# PowerDevices.net
KiCad netlist of a schematic drawn in Altium Designer
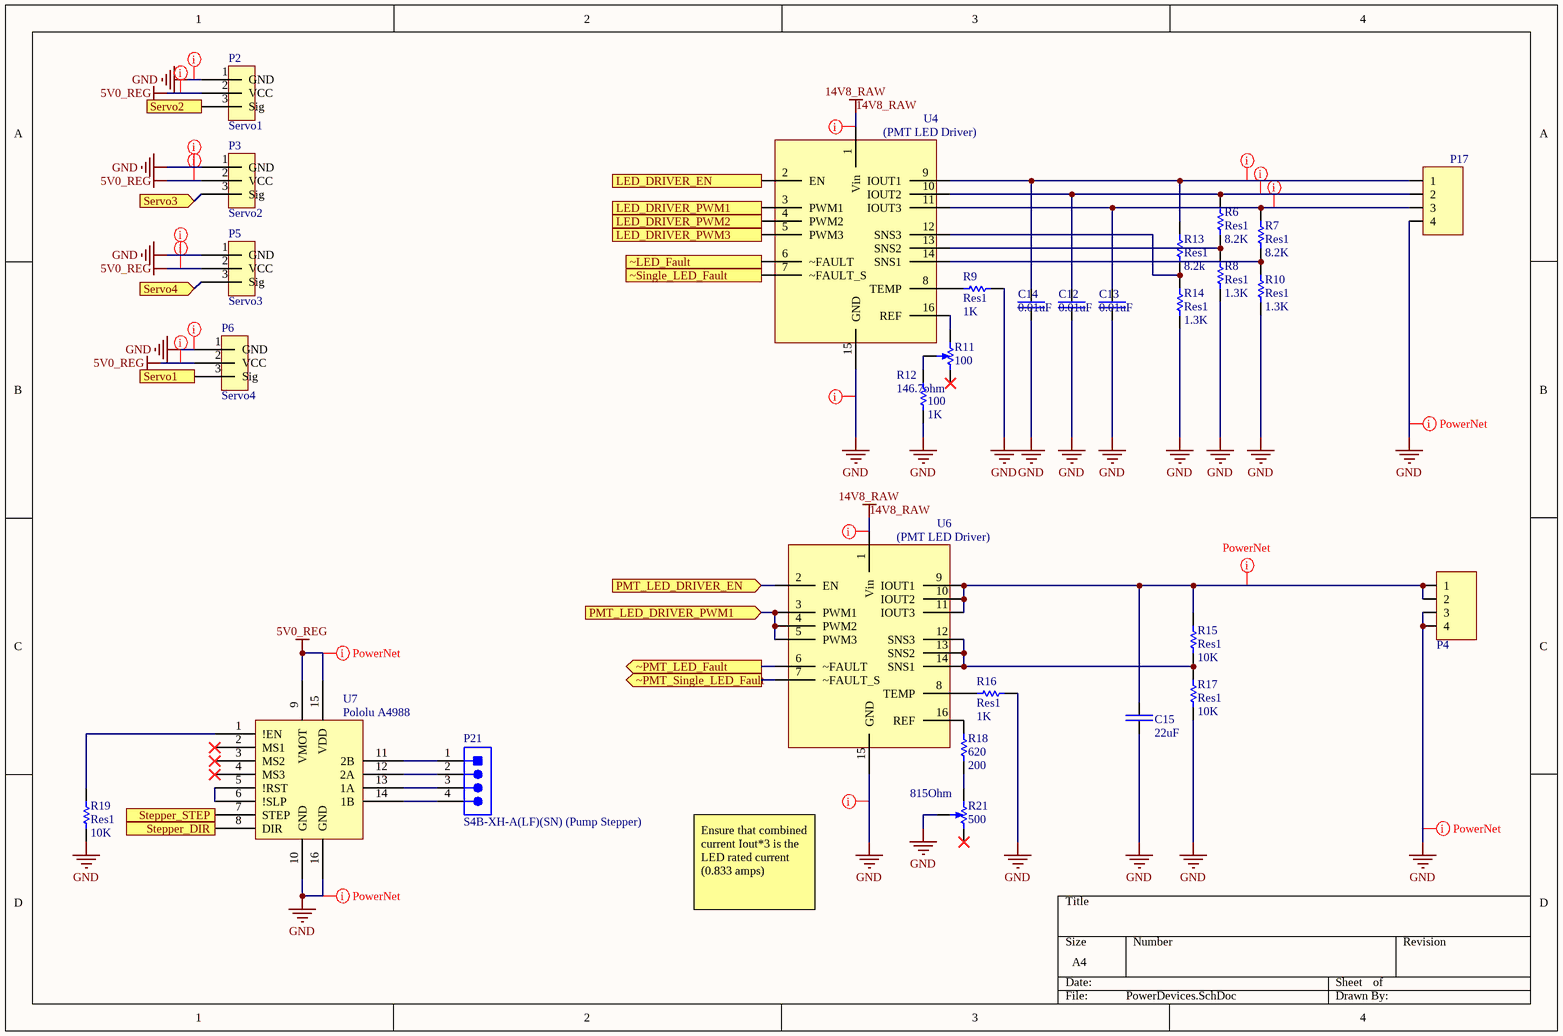
[diagram p0: PowerDevices.SchDoc]

(export (version "E")
  (design (tool "Eeschema 10.0.6"))
  (components
    (comp (ref "C12")
      (value "0.01uF")
      (footprint "0.01uF capacitor")
      (description "Cap Ceramic 0.01uF 250V X7R 10% Pad SMD 0603 125C Automotive T/R")
      (fields (field (name "TOLERANCE") "10%"))
      (libsource (lib "RSX_Capacitors") (part "C0603C103KARACAUTO"))
    )
    (comp (ref "C13")
      (value "0.01uF")
      (footprint "0.01uF capacitor")
      (description "Cap Ceramic 0.01uF 250V X7R 10% Pad SMD 0603 125C Automotive T/R")
      (fields (field (name "TOLERANCE") "10%"))
      (libsource (lib "RSX_Capacitors") (part "C0603C103KARACAUTO"))
    )
    (comp (ref "C14")
      (value "0.01uF")
      (footprint "0.01uF capacitor")
      (description "Cap Ceramic 0.01uF 250V X7R 10% Pad SMD 0603 125C Automotive T/R")
      (fields (field (name "TOLERANCE") "10%"))
      (libsource (lib "RSX_Capacitors") (part "C0603C103KARACAUTO"))
    )
    (comp (ref "C15")
      (value "22uF")
      (footprint "22uF Capacitor")
      (description "Cap Ceramic 22uF 25V X7R 10% SMD 1210 125C Embossed T/R")
      (fields (field (name "TOLERANCE") "10%") (field (name "VOLTAGE") "25V"))
      (libsource (lib "RSX_Capacitors") (part "GRM32ER71E226KE15L"))
    )
    (comp (ref "P2") (value "Servo1") (footprint "Header3") (libsource (lib "DUE") (part "Header3")))
    (comp (ref "P3") (value "Servo2") (footprint "Header3") (libsource (lib "DUE") (part "Header3")))
    (comp (ref "P4")
      (value "Mini-Fit Jr 4 Pos")
      (footprint "MOLEX 0039281043")
      (libsource (lib "RSX_Connectors") (part "Molex 0039281043"))
    )
    (comp (ref "P5") (value "Servo3") (footprint "Header3") (libsource (lib "DUE") (part "Header3")))
    (comp (ref "P6") (value "Servo4") (footprint "Header3") (libsource (lib "DUE") (part "Header3")))
    (comp (ref "P17")
      (value "Mini-Fit Jr 4 Pos")
      (footprint "MOLEX 0039281043")
      (libsource (lib "RSX_Connectors") (part "Molex 0039281043"))
    )
    (comp (ref "P21")
      (value "S4B-XH-A(LF)(SN) (Pump Stepper)")
      (footprint "JST-S4B-XH-A(LF)(SN)_V")
      (libsource (lib "Altium Content Vault") (part "CN-1P-M-R4"))
    )
    (comp (ref "R6")
      (value "Res1")
      (footprint "RESC1608X06N_0603")
      (description "Resistor")
      (fields (field (name "ALTIUM_VALUE") "8.2K") (field (name "PUBLISHER") "Altium Limited"))
      (libsource (lib "RSX_Resistors") (part "Res1"))
    )
    (comp (ref "R7")
      (value "Res1")
      (footprint "RESC1608X06N_0603")
      (description "Resistor")
      (fields (field (name "ALTIUM_VALUE") "8.2K") (field (name "PUBLISHER") "Altium Limited"))
      (libsource (lib "RSX_Resistors") (part "Res1"))
    )
    (comp (ref "R8")
      (value "Res1")
      (footprint "RESC1608X06N_0603")
      (description "Resistor")
      (fields (field (name "ALTIUM_VALUE") "1.3K") (field (name "PUBLISHER") "Altium Limited"))
      (libsource (lib "RSX_Resistors") (part "Res1"))
    )
    (comp (ref "R9")
      (value "Res1")
      (footprint "RESC1608X06N_0603")
      (description "Resistor")
      (fields (field (name "ALTIUM_VALUE") "1K") (field (name "PUBLISHER") "Altium Limited"))
      (libsource (lib "RSX_Resistors") (part "Res1"))
    )
    (comp (ref "R10")
      (value "Res1")
      (footprint "RESC1608X06N_0603")
      (description "Resistor")
      (fields (field (name "ALTIUM_VALUE") "1.3K") (field (name "PUBLISHER") "Altium Limited"))
      (libsource (lib "RSX_Resistors") (part "Res1"))
    )
    (comp (ref "R11")
      (value "100")
      (footprint "POT-LV10")
      (description "Square Trimming Potentiometer (100 ohm)")
      (fields (field (name "PUBLISHER") "Altium Limited"))
      (libsource (lib "Miscellaneous Devices") (part "RPot SM"))
    )
    (comp (ref "R12")
      (value "100")
      (footprint "RESC1608X06N_0603")
      (description "Resistor")
      (fields (field (name "ALTIUM_VALUE") "1K") (field (name "PUBLISHER") "Altium Limited"))
      (libsource (lib "RSX_Resistors") (part "Res1"))
    )
    (comp (ref "R13")
      (value "Res1")
      (footprint "RESC1608X06N_0603")
      (description "Resistor")
      (fields (field (name "ALTIUM_VALUE") "8.2k") (field (name "PUBLISHER") "Altium Limited"))
      (libsource (lib "RSX_Resistors") (part "Res1"))
    )
    (comp (ref "R14")
      (value "Res1")
      (footprint "RESC1608X06N_0603")
      (description "Resistor")
      (fields (field (name "ALTIUM_VALUE") "1.3K") (field (name "PUBLISHER") "Altium Limited"))
      (libsource (lib "RSX_Resistors") (part "Res1"))
    )
    (comp (ref "R15")
      (value "Res1")
      (footprint "RESC1608X06N_0603")
      (description "Resistor")
      (fields (field (name "ALTIUM_VALUE") "10K") (field (name "PUBLISHER") "Altium Limited"))
      (libsource (lib "RSX_Resistors") (part "Res1"))
    )
    (comp (ref "R16")
      (value "Res1")
      (footprint "RESC1608X06N_0603")
      (description "Resistor")
      (fields (field (name "ALTIUM_VALUE") "1K") (field (name "PUBLISHER") "Altium Limited"))
      (libsource (lib "RSX_Resistors") (part "Res1"))
    )
    (comp (ref "R17")
      (value "Res1")
      (footprint "RESC1608X06N_0603")
      (description "Resistor")
      (fields (field (name "ALTIUM_VALUE") "10K") (field (name "PUBLISHER") "Altium Limited"))
      (libsource (lib "RSX_Resistors") (part "Res1"))
    )
    (comp (ref "R18")
      (value "620")
      (footprint "RESC1608X06N_0603")
      (description "Resistor")
      (fields (field (name "ALTIUM_VALUE") "200") (field (name "PUBLISHER") "Altium Limited"))
      (libsource (lib "RSX_Resistors") (part "Res1"))
    )
    (comp (ref "R19")
      (value "Res1")
      (footprint "RESC1608X06N_0603")
      (description "Resistor")
      (fields (field (name "ALTIUM_VALUE") "10K") (field (name "PUBLISHER") "Altium Limited"))
      (libsource (lib "RSX_Resistors") (part "Res1"))
    )
    (comp (ref "R21")
      (value "500")
      (footprint "POT-LV10")
      (description "Square Trimming Potentiometer (100 ohm)")
      (fields (field (name "PUBLISHER") "Altium Limited"))
      (libsource (lib "Miscellaneous Devices") (part "RPot SM"))
    )
    (comp (ref "U4")
      (value "(PMT LED Driver)")
      (footprint "HTSSOP16")
      (libsource (lib "ScienceComponents") (part "TPS92630QPWPRQ1"))
    )
    (comp (ref "U6")
      (value "(PMT LED Driver)")
      (footprint "HTSSOP16")
      (libsource (lib "ScienceComponents") (part "TPS92630QPWPRQ1"))
    )
    (comp (ref "U7")
      (value "Pololu A4988")
      (footprint "Stepper Driver Pololu A4988")
      (libsource (lib "ScienceComponents") (part "stepper driver Pololu a4988"))
    )
  )
  (nets
    (net (code "1") (name "/LED_DRIVER_EN") (class "Default")
      (node (ref "U4") (pin "2") (pinfunction "EN_2") (pintype "passive"))
    )
    (net (code "2") (name "/LED_DRIVER_PWM1") (class "Default")
      (node (ref "U4") (pin "3") (pinfunction "PWM1_3") (pintype "passive"))
    )
    (net (code "3") (name "/LED_DRIVER_PWM2") (class "Default")
      (node (ref "U4") (pin "4") (pinfunction "PWM2_4") (pintype "passive"))
    )
    (net (code "4") (name "/LED_DRIVER_PWM3") (class "Default")
      (node (ref "U4") (pin "5") (pinfunction "PWM3_5") (pintype "passive"))
    )
    (net (code "5") (name "/PMT_LED_DRIVER_EN") (class "Default")
      (node (ref "U6") (pin "2") (pinfunction "EN_2") (pintype "passive"))
    )
    (net (code "6") (name "/PMT_LED_DRIVER_PWM1") (class "Default")
      (node (ref "U6") (pin "3") (pinfunction "PWM1_3") (pintype "passive"))
      (node (ref "U6") (pin "4") (pinfunction "PWM2_4") (pintype "passive"))
      (node (ref "U6") (pin "5") (pinfunction "PWM3_5") (pintype "passive"))
    )
    (net (code "7") (name "/Servo1") (class "Default")
      (node (ref "P6") (pin "3") (pinfunction "Sig_3") (pintype "passive"))
    )
    (net (code "8") (name "/Servo2") (class "Default")
      (node (ref "P2") (pin "3") (pinfunction "Sig_3") (pintype "passive"))
    )
    (net (code "9") (name "/Servo3") (class "Default")
      (node (ref "P3") (pin "3") (pinfunction "Sig_3") (pintype "passive"))
    )
    (net (code "10") (name "/Servo4") (class "Default")
      (node (ref "P5") (pin "3") (pinfunction "Sig_3") (pintype "passive"))
    )
    (net (code "11") (name "/Stepper_DIR") (class "Default")
      (node (ref "U7") (pin "8") (pinfunction "DIR_8") (pintype "passive"))
    )
    (net (code "12") (name "/Stepper_STEP") (class "Default")
      (node (ref "U7") (pin "7") (pinfunction "STEP_7") (pintype "passive"))
    )
    (net (code "13") (name "/~LED_Fault") (class "Default")
      (node (ref "U4") (pin "6") (pinfunction "~FAULT_6") (pintype "passive"))
    )
    (net (code "14") (name "/~PMT_LED_Fault") (class "Default")
      (node (ref "U6") (pin "6") (pinfunction "~FAULT_6") (pintype "passive"))
    )
    (net (code "15") (name "/~PMT_Single_LED_Fault") (class "Default")
      (node (ref "U6") (pin "7") (pinfunction "~FAULT_S_7") (pintype "passive"))
    )
    (net (code "16") (name "/~Single_LED_Fault") (class "Default")
      (node (ref "U4") (pin "7") (pinfunction "~FAULT_S_7") (pintype "passive"))
    )
    (net (code "17") (name "5V0_REG") (class "Default")
      (node (ref "P2") (pin "2") (pinfunction "VCC_2") (pintype "passive"))
      (node (ref "P3") (pin "2") (pinfunction "VCC_2") (pintype "passive"))
      (node (ref "P5") (pin "2") (pinfunction "VCC_2") (pintype "passive"))
      (node (ref "P6") (pin "2") (pinfunction "VCC_2") (pintype "passive"))
      (node (ref "U7") (pin "15") (pinfunction "VDD_15") (pintype "passive"))
      (node (ref "U7") (pin "9") (pinfunction "VMOT_9") (pintype "passive"))
    )
    (net (code "18") (name "14V8_RAW") (class "Default")
      (node (ref "U4") (pin "1") (pinfunction "Vin_1") (pintype "passive"))
      (node (ref "U6") (pin "1") (pinfunction "Vin_1") (pintype "passive"))
    )
    (net (code "19") (name "GND") (class "Default")
      (node (ref "C12") (pin "1") (pinfunction "15_1") (pintype "passive"))
      (node (ref "C13") (pin "1") (pinfunction "15_1") (pintype "passive"))
      (node (ref "C14") (pin "1") (pinfunction "15_1") (pintype "passive"))
      (node (ref "C15") (pin "1") (pinfunction "15_1") (pintype "passive"))
      (node (ref "P17") (pin "4") (pinfunction "4_4") (pintype "passive"))
      (node (ref "P2") (pin "1") (pinfunction "GND_1") (pintype "passive"))
      (node (ref "P3") (pin "1") (pinfunction "GND_1") (pintype "passive"))
      (node (ref "P4") (pin "3") (pinfunction "3_3") (pintype "passive"))
      (node (ref "P4") (pin "4") (pinfunction "4_4") (pintype "passive"))
      (node (ref "P5") (pin "1") (pinfunction "GND_1") (pintype "passive"))
      (node (ref "P6") (pin "1") (pinfunction "GND_1") (pintype "passive"))
      (node (ref "R10") (pin "1") (pinfunction "1_1") (pintype "passive"))
      (node (ref "R12") (pin "2") (pinfunction "2_2") (pintype "passive"))
      (node (ref "R14") (pin "1") (pinfunction "1_1") (pintype "passive"))
      (node (ref "R16") (pin "2") (pinfunction "2_2") (pintype "passive"))
      (node (ref "R17") (pin "1") (pinfunction "1_1") (pintype "passive"))
      (node (ref "R19") (pin "1") (pinfunction "1_1") (pintype "passive"))
      (node (ref "R21") (pin "W") (pinfunction "W_W") (pintype "passive"))
      (node (ref "R8") (pin "1") (pinfunction "1_1") (pintype "passive"))
      (node (ref "R9") (pin "2") (pinfunction "2_2") (pintype "passive"))
      (node (ref "U4") (pin "15") (pinfunction "GND_15") (pintype "passive"))
      (node (ref "U6") (pin "15") (pinfunction "GND_15") (pintype "passive"))
      (node (ref "U7") (pin "10") (pinfunction "GND_10") (pintype "passive"))
      (node (ref "U7") (pin "16") (pinfunction "GND_16") (pintype "passive"))
    )
    (net (code "20") (name "Net-(C12-16)") (class "Default")
      (node (ref "C12") (pin "2") (pinfunction "16_2") (pintype "passive"))
      (node (ref "P17") (pin "2") (pinfunction "2_2") (pintype "passive"))
      (node (ref "R6") (pin "2") (pinfunction "2_2") (pintype "passive"))
      (node (ref "U4") (pin "10") (pinfunction "IOUT2_10") (pintype "passive"))
    )
    (net (code "21") (name "Net-(C13-16)") (class "Default")
      (node (ref "C13") (pin "2") (pinfunction "16_2") (pintype "passive"))
      (node (ref "P17") (pin "3") (pinfunction "3_3") (pintype "passive"))
      (node (ref "R7") (pin "2") (pinfunction "2_2") (pintype "passive"))
      (node (ref "U4") (pin "11") (pinfunction "IOUT3_11") (pintype "passive"))
    )
    (net (code "22") (name "Net-(C14-16)") (class "Default")
      (node (ref "C14") (pin "2") (pinfunction "16_2") (pintype "passive"))
      (node (ref "P17") (pin "1") (pinfunction "1_1") (pintype "passive"))
      (node (ref "R13") (pin "1") (pinfunction "1_1") (pintype "passive"))
      (node (ref "U4") (pin "9") (pinfunction "IOUT1_9") (pintype "passive"))
    )
    (net (code "23") (name "Net-(C15-16)") (class "Default")
      (node (ref "C15") (pin "2") (pinfunction "16_2") (pintype "passive"))
      (node (ref "P4") (pin "1") (pinfunction "1_1") (pintype "passive"))
      (node (ref "P4") (pin "2") (pinfunction "2_2") (pintype "passive"))
      (node (ref "R15") (pin "1") (pinfunction "1_1") (pintype "passive"))
      (node (ref "U6") (pin "10") (pinfunction "IOUT2_10") (pintype "passive"))
      (node (ref "U6") (pin "11") (pinfunction "IOUT3_11") (pintype "passive"))
      (node (ref "U6") (pin "9") (pinfunction "IOUT1_9") (pintype "passive"))
    )
    (net (code "24") (name "Net-(R11--)") (class "Default")
      (node (ref "R11") (pin "CCW") (pinfunction "-_CCW") (pintype "passive"))
      (node (ref "U4") (pin "16") (pinfunction "REF_16") (pintype "passive"))
    )
    (net (code "25") (name "Net-(R11-PadW)") (class "Default")
      (node (ref "R11") (pin "W") (pinfunction "W_W") (pintype "passive"))
      (node (ref "R12") (pin "1") (pinfunction "1_1") (pintype "passive"))
    )
    (net (code "26") (name "Net-(R21--)") (class "Default")
      (node (ref "R18") (pin "1") (pinfunction "1_1") (pintype "passive"))
      (node (ref "R21") (pin "CCW") (pinfunction "-_CCW") (pintype "passive"))
    )
    (net (code "27") (name "Net-(U4-SNS1)") (class "Default")
      (node (ref "R10") (pin "2") (pinfunction "2_2") (pintype "passive"))
      (node (ref "R7") (pin "1") (pinfunction "1_1") (pintype "passive"))
      (node (ref "U4") (pin "14") (pinfunction "SNS1_14") (pintype "passive"))
    )
    (net (code "28") (name "Net-(U4-SNS2)") (class "Default")
      (node (ref "R6") (pin "1") (pinfunction "1_1") (pintype "passive"))
      (node (ref "R8") (pin "2") (pinfunction "2_2") (pintype "passive"))
      (node (ref "U4") (pin "13") (pinfunction "SNS2_13") (pintype "passive"))
    )
    (net (code "29") (name "Net-(U4-SNS3)") (class "Default")
      (node (ref "R13") (pin "2") (pinfunction "2_2") (pintype "passive"))
      (node (ref "R14") (pin "2") (pinfunction "2_2") (pintype "passive"))
      (node (ref "U4") (pin "12") (pinfunction "SNS3_12") (pintype "passive"))
    )
    (net (code "30") (name "Net-(U4-TEMP)") (class "Default")
      (node (ref "R9") (pin "1") (pinfunction "1_1") (pintype "passive"))
      (node (ref "U4") (pin "8") (pinfunction "TEMP_8") (pintype "passive"))
    )
    (net (code "31") (name "Net-(U6-REF)") (class "Default")
      (node (ref "R18") (pin "2") (pinfunction "2_2") (pintype "passive"))
      (node (ref "U6") (pin "16") (pinfunction "REF_16") (pintype "passive"))
    )
    (net (code "32") (name "Net-(U6-SNS1)") (class "Default")
      (node (ref "R15") (pin "2") (pinfunction "2_2") (pintype "passive"))
      (node (ref "R17") (pin "2") (pinfunction "2_2") (pintype "passive"))
      (node (ref "U6") (pin "12") (pinfunction "SNS3_12") (pintype "passive"))
      (node (ref "U6") (pin "13") (pinfunction "SNS2_13") (pintype "passive"))
      (node (ref "U6") (pin "14") (pinfunction "SNS1_14") (pintype "passive"))
    )
    (net (code "33") (name "Net-(U6-TEMP)") (class "Default")
      (node (ref "R16") (pin "1") (pinfunction "1_1") (pintype "passive"))
      (node (ref "U6") (pin "8") (pinfunction "TEMP_8") (pintype "passive"))
    )
    (net (code "34") (name "Net-(U7-!EN)") (class "Default")
      (node (ref "R19") (pin "2") (pinfunction "2_2") (pintype "passive"))
      (node (ref "U7") (pin "1") (pinfunction "!EN_1") (pintype "passive"))
    )
    (net (code "35") (name "Net-(U7-!RST)") (class "Default")
      (node (ref "U7") (pin "5") (pinfunction "!RST_5") (pintype "passive"))
      (node (ref "U7") (pin "6") (pinfunction "!SLP_6") (pintype "passive"))
    )
    (net (code "36") (name "Net-(U7-1A)") (class "Default")
      (node (ref "P21") (pin "3") (pinfunction "3_3") (pintype "passive"))
      (node (ref "U7") (pin "13") (pinfunction "1A_13") (pintype "passive"))
    )
    (net (code "37") (name "Net-(U7-1B)") (class "Default")
      (node (ref "P21") (pin "4") (pinfunction "4_4") (pintype "passive"))
      (node (ref "U7") (pin "14") (pinfunction "1B_14") (pintype "passive"))
    )
    (net (code "38") (name "Net-(U7-2A)") (class "Default")
      (node (ref "P21") (pin "2") (pinfunction "2_2") (pintype "passive"))
      (node (ref "U7") (pin "12") (pinfunction "2A_12") (pintype "passive"))
    )
    (net (code "39") (name "Net-(U7-2B)") (class "Default")
      (node (ref "P21") (pin "1") (pinfunction "1_1") (pintype "passive"))
      (node (ref "U7") (pin "11") (pinfunction "2B_11") (pintype "passive"))
    )
    (net (code "40") (name "unconnected-(R11-+-PadCW)") (class "Default")
      (node (ref "R11") (pin "CW") (pinfunction "+_CW") (pintype "passive+no_connect"))
    )
    (net (code "41") (name "unconnected-(R21-+-PadCW)") (class "Default")
      (node (ref "R21") (pin "CW") (pinfunction "+_CW") (pintype "passive+no_connect"))
    )
    (net (code "42") (name "unconnected-(U7-MS1-Pad2)") (class "Default")
      (node (ref "U7") (pin "2") (pinfunction "MS1_2") (pintype "passive+no_connect"))
    )
    (net (code "43") (name "unconnected-(U7-MS2-Pad3)") (class "Default")
      (node (ref "U7") (pin "3") (pinfunction "MS2_3") (pintype "passive+no_connect"))
    )
    (net (code "44") (name "unconnected-(U7-MS3-Pad4)") (class "Default")
      (node (ref "U7") (pin "4") (pinfunction "MS3_4") (pintype "passive+no_connect"))
    )
  )
)
